# WifiNode_Per_R00.net
KiCad netlist of a schematic drawn in Altium Designer
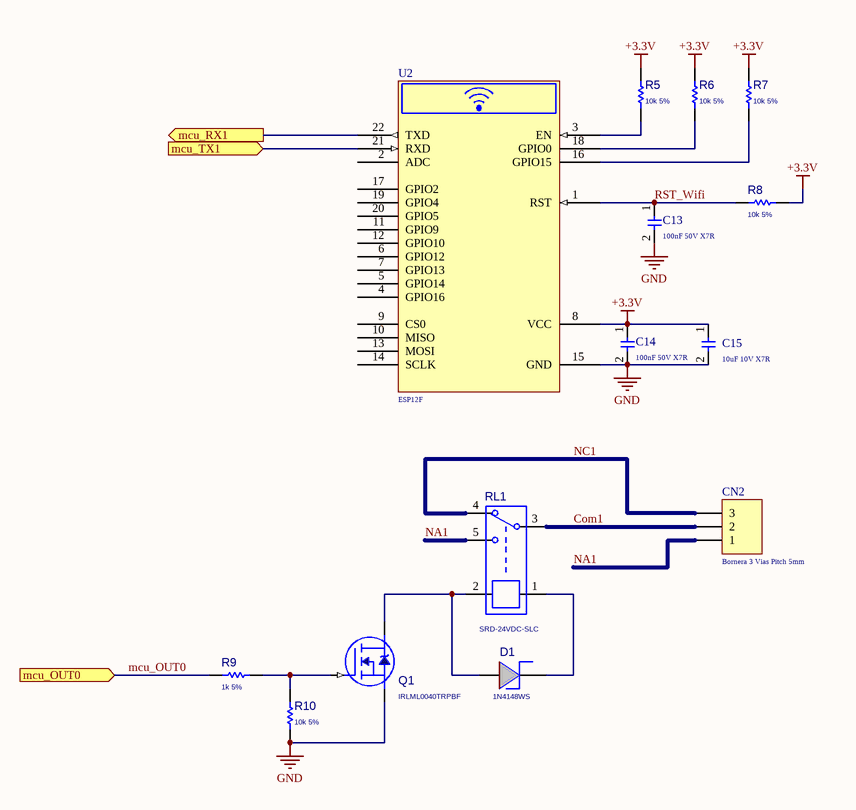
[diagram p0: WifiNode_Per_R00.SchDoc]

(export (version "E")
  (design (tool "Eeschema 10.0.6"))
  (components
    (comp (ref "C13")
      (value "100nF 50V X7R")
      (footprint "C_0805")
      (description "Not polarized capacitor")
      (libsource (lib "IDCI_TP1_SFARA") (part "CAP_NP"))
    )
    (comp (ref "C14")
      (value "100nF 50V X7R")
      (footprint "C_0805")
      (description "Not polarized capacitor")
      (libsource (lib "IDCI_TP1_SFARA") (part "CAP_NP"))
    )
    (comp (ref "C15")
      (value "10uF 10V X7R")
      (footprint "C_0805")
      (description "Not polarized capacitor")
      (libsource (lib "IDCI_TP1_SFARA") (part "CAP_NP"))
    )
    (comp (ref "CN2")
      (value "Bornera 3 Vias Pitch 5mm")
      (footprint "TerminalBlock_1x3_P5mm")
      (description "Connector Generic 3 Vias")
      (libsource (lib "IDCI_TP1_SFARA") (part "CONN_03P"))
    )
    (comp (ref "D1")
      (value "1N4148WS")
      (footprint "D_0805")
      (description "Diode Shottky")
      (libsource (lib "IDCI_TP1_SFARA") (part "DIODO_SH"))
    )
    (comp (ref "Q1")
      (value "IRLML0040TRPBF")
      (footprint "SOT_23")
      (description "Mosfet N-Ch")
      (libsource (lib "IDCI_TP1_SFARA") (part "N_MOSFET_SOT23"))
    )
    (comp (ref "R5")
      (value "10k 5%")
      (footprint "R_0805")
      (description "Resistor")
      (libsource (lib "IDCI_TP1_SFARA") (part "Res1"))
    )
    (comp (ref "R6")
      (value "10k 5%")
      (footprint "R_0805")
      (description "Resistor")
      (libsource (lib "IDCI_TP1_SFARA") (part "Res1"))
    )
    (comp (ref "R7")
      (value "10k 5%")
      (footprint "R_0805")
      (description "Resistor")
      (libsource (lib "IDCI_TP1_SFARA") (part "Res1"))
    )
    (comp (ref "R8")
      (value "10k 5%")
      (footprint "R_0805")
      (description "Resistor")
      (libsource (lib "IDCI_TP1_SFARA") (part "Res1"))
    )
    (comp (ref "R9")
      (value "1k 5%")
      (footprint "C_0805")
      (description "Resistor")
      (libsource (lib "IDCI_TP1_SFARA") (part "Res1"))
    )
    (comp (ref "R10")
      (value "10k 5%")
      (footprint "C_0805")
      (description "Resistor")
      (libsource (lib "IDCI_TP1_SFARA") (part "Res1"))
    )
    (comp (ref "RL1")
      (value "SRD-24VDC-SLC")
      (footprint "943-1C")
      (description "Relay SPDT")
      (libsource (lib "IDCI_TP1_SFARA") (part "RELAY SPDT"))
    )
    (comp (ref "U2")
      (value "ESP12F")
      (footprint "ESP12F")
      (description "Wifi Module")
      (libsource (lib "IDCI_TP1_SFARA") (part "ESP12F Wifi Module"))
    )
  )
  (nets
    (net (code "1") (name "+3.3V") (class "Default")
      (node (ref "C14") (pin "1") (pintype "passive"))
      (node (ref "C15") (pin "1") (pintype "passive"))
      (node (ref "R5") (pin "2") (pinfunction "2_2") (pintype "passive"))
      (node (ref "R6") (pin "2") (pinfunction "2_2") (pintype "passive"))
      (node (ref "R7") (pin "2") (pinfunction "2_2") (pintype "passive"))
      (node (ref "R8") (pin "1") (pinfunction "1_1") (pintype "passive"))
      (node (ref "U2") (pin "8") (pinfunction "VCC_8") (pintype "power_in"))
    )
    (net (code "2") (name "/Com1") (class "Default")
      (node (ref "CN2") (pin "2") (pinfunction "2_2") (pintype "passive"))
      (node (ref "RL1") (pin "3") (pinfunction "3_3") (pintype "passive"))
    )
    (net (code "3") (name "/NA1") (class "Default")
      (node (ref "CN2") (pin "1") (pinfunction "1_1") (pintype "passive"))
      (node (ref "RL1") (pin "5") (pinfunction "5_5") (pintype "passive"))
    )
    (net (code "4") (name "/NC1") (class "Default")
      (node (ref "CN2") (pin "3") (pinfunction "3_3") (pintype "passive"))
      (node (ref "RL1") (pin "4") (pinfunction "4_4") (pintype "passive"))
    )
    (net (code "5") (name "/RST_Wifi") (class "Default")
      (node (ref "C13") (pin "1") (pintype "passive"))
      (node (ref "R8") (pin "2") (pinfunction "2_2") (pintype "passive"))
      (node (ref "U2") (pin "1") (pinfunction "RST_1") (pintype "input"))
    )
    (net (code "6") (name "/mcu_OUT0") (class "Default")
      (node (ref "R9") (pin "2") (pinfunction "2_2") (pintype "passive"))
    )
    (net (code "7") (name "/mcu_RX1") (class "Default")
      (node (ref "U2") (pin "22") (pinfunction "TXD_22") (pintype "output"))
    )
    (net (code "8") (name "/mcu_TX1") (class "Default")
      (node (ref "U2") (pin "21") (pinfunction "RXD_21") (pintype "input"))
    )
    (net (code "9") (name "GND") (class "Default")
      (node (ref "C13") (pin "2") (pintype "passive"))
      (node (ref "C14") (pin "2") (pintype "passive"))
      (node (ref "C15") (pin "2") (pintype "passive"))
      (node (ref "Q1") (pin "2") (pinfunction "SOURCE_2") (pintype "passive"))
      (node (ref "R10") (pin "1") (pinfunction "1_1") (pintype "passive"))
      (node (ref "U2") (pin "15") (pinfunction "GND_15") (pintype "power_in"))
    )
    (net (code "10") (name "Net-(D1-A)") (class "Default")
      (node (ref "D1") (pin "1") (pinfunction "A_1") (pintype "passive"))
      (node (ref "Q1") (pin "3") (pinfunction "DRAIN_3") (pintype "passive"))
      (node (ref "RL1") (pin "2") (pinfunction "2_2") (pintype "passive"))
    )
    (net (code "11") (name "Net-(D1-K)") (class "Default")
      (node (ref "D1") (pin "2") (pinfunction "K_2") (pintype "passive"))
      (node (ref "RL1") (pin "1") (pinfunction "1_1") (pintype "passive"))
    )
    (net (code "12") (name "Net-(Q1-GATE)") (class "Default")
      (node (ref "Q1") (pin "1") (pinfunction "GATE_1") (pintype "input"))
      (node (ref "R10") (pin "2") (pinfunction "2_2") (pintype "passive"))
      (node (ref "R9") (pin "1") (pinfunction "1_1") (pintype "passive"))
    )
    (net (code "13") (name "Net-(U2-EN)") (class "Default")
      (node (ref "R5") (pin "1") (pinfunction "1_1") (pintype "passive"))
      (node (ref "U2") (pin "3") (pinfunction "EN_3") (pintype "input"))
    )
    (net (code "14") (name "Net-(U2-GPIO0)") (class "Default")
      (node (ref "R6") (pin "1") (pinfunction "1_1") (pintype "passive"))
      (node (ref "U2") (pin "18") (pinfunction "GPIO0_18") (pintype "passive"))
    )
    (net (code "15") (name "Net-(U2-GPIO15)") (class "Default")
      (node (ref "R7") (pin "1") (pinfunction "1_1") (pintype "passive"))
      (node (ref "U2") (pin "16") (pinfunction "GPIO15_16") (pintype "passive"))
    )
    (net (code "16") (name "unconnected-(U2-ADC-Pad2)") (class "Default")
      (node (ref "U2") (pin "2") (pinfunction "ADC_2") (pintype "passive"))
    )
    (net (code "17") (name "unconnected-(U2-CS0-Pad9)") (class "Default")
      (node (ref "U2") (pin "9") (pinfunction "CS0_9") (pintype "passive"))
    )
    (net (code "18") (name "unconnected-(U2-GPIO2-Pad17)") (class "Default")
      (node (ref "U2") (pin "17") (pinfunction "GPIO2_17") (pintype "passive"))
    )
    (net (code "19") (name "unconnected-(U2-GPIO4-Pad19)") (class "Default")
      (node (ref "U2") (pin "19") (pinfunction "GPIO4_19") (pintype "passive"))
    )
    (net (code "20") (name "unconnected-(U2-GPIO5-Pad20)") (class "Default")
      (node (ref "U2") (pin "20") (pinfunction "GPIO5_20") (pintype "passive"))
    )
    (net (code "21") (name "unconnected-(U2-GPIO9-Pad11)") (class "Default")
      (node (ref "U2") (pin "11") (pinfunction "GPIO9_11") (pintype "passive"))
    )
    (net (code "22") (name "unconnected-(U2-GPIO10-Pad12)") (class "Default")
      (node (ref "U2") (pin "12") (pinfunction "GPIO10_12") (pintype "passive"))
    )
    (net (code "23") (name "unconnected-(U2-GPIO12-Pad6)") (class "Default")
      (node (ref "U2") (pin "6") (pinfunction "GPIO12_6") (pintype "passive"))
    )
    (net (code "24") (name "unconnected-(U2-GPIO13-Pad7)") (class "Default")
      (node (ref "U2") (pin "7") (pinfunction "GPIO13_7") (pintype "passive"))
    )
    (net (code "25") (name "unconnected-(U2-GPIO14-Pad5)") (class "Default")
      (node (ref "U2") (pin "5") (pinfunction "GPIO14_5") (pintype "passive"))
    )
    (net (code "26") (name "unconnected-(U2-GPIO16-Pad4)") (class "Default")
      (node (ref "U2") (pin "4") (pinfunction "GPIO16_4") (pintype "passive"))
    )
    (net (code "27") (name "unconnected-(U2-MISO-Pad10)") (class "Default")
      (node (ref "U2") (pin "10") (pinfunction "MISO_10") (pintype "passive"))
    )
    (net (code "28") (name "unconnected-(U2-MOSI-Pad13)") (class "Default")
      (node (ref "U2") (pin "13") (pinfunction "MOSI_13") (pintype "passive"))
    )
    (net (code "29") (name "unconnected-(U2-SCLK-Pad14)") (class "Default")
      (node (ref "U2") (pin "14") (pinfunction "SCLK_14") (pintype "passive"))
    )
  )
)
